# 3_waffling80-NMB_mcu.net
KiCad netlist of a schematic drawn in Altium Designer
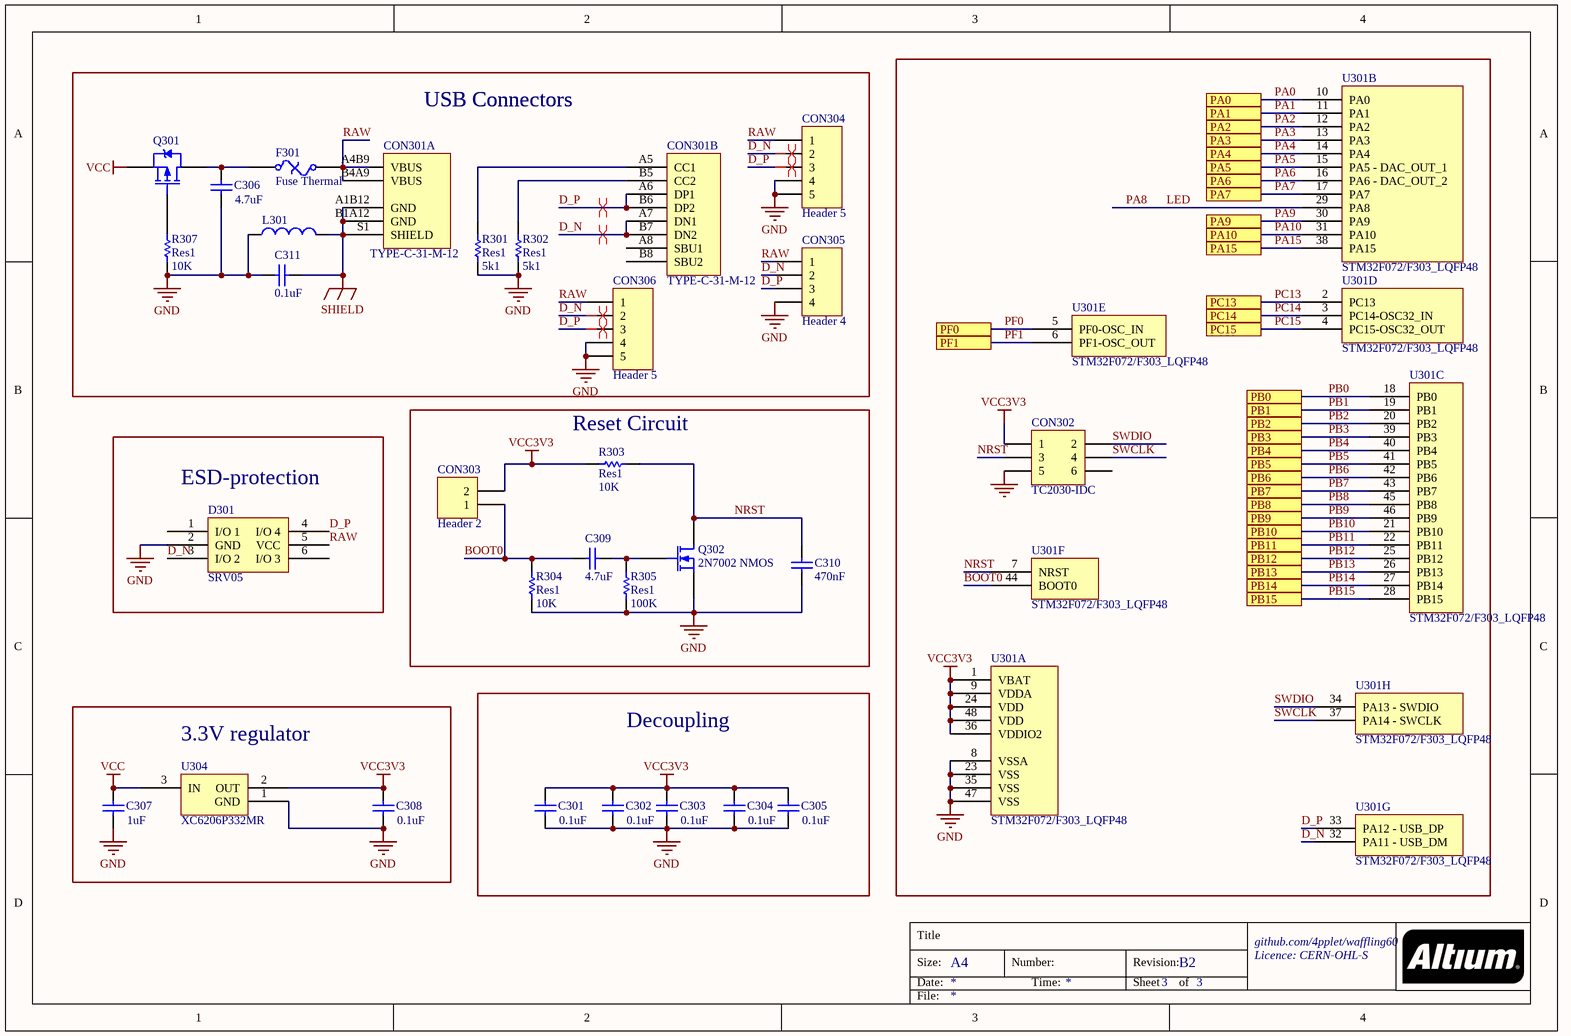
[diagram p0: 3_waffling80-NMB_mcu.SchDoc]

(export (version "E")
  (design (tool "Eeschema 10.0.6"))
  (components
    (comp (ref "C301")
      (value "0.1uF")
      (footprint "C0603[1608]")
      (description "Capacitor")
      (fields (field (name "LCSC PART #") "C14663") (field (name "MRF.PART") "CC0603KRX7R9BB104"))
      (libsource (lib "Miscellaneous Devices") (part "Cap"))
    )
    (comp (ref "C302")
      (value "0.1uF")
      (footprint "C0603[1608]")
      (description "Capacitor")
      (fields (field (name "LCSC PART #") "C14663") (field (name "MRF.PART") "CC0603KRX7R9BB104"))
      (libsource (lib "Miscellaneous Devices") (part "Cap"))
    )
    (comp (ref "C303")
      (value "0.1uF")
      (footprint "C0603[1608]")
      (description "Capacitor")
      (fields (field (name "LCSC PART #") "C14663") (field (name "MRF.PART") "CC0603KRX7R9BB104"))
      (libsource (lib "Miscellaneous Devices") (part "Cap"))
    )
    (comp (ref "C304")
      (value "0.1uF")
      (footprint "C0603[1608]")
      (description "Capacitor")
      (fields (field (name "LCSC PART #") "C14663") (field (name "MRF.PART") "CC0603KRX7R9BB104"))
      (libsource (lib "Miscellaneous Devices") (part "Cap"))
    )
    (comp (ref "C305")
      (value "0.1uF")
      (footprint "C0603[1608]")
      (description "Capacitor")
      (fields (field (name "LCSC PART #") "C14663") (field (name "MRF.PART") "CC0603KRX7R9BB104"))
      (libsource (lib "Miscellaneous Devices") (part "Cap"))
    )
    (comp (ref "C306")
      (value "4.7uF")
      (footprint "C0603[1608]")
      (description "Capacitor")
      (fields (field (name "LCSC PART #") "C19666") (field (name "MRF.PART") "CL10A475KO8NNNC"))
      (libsource (lib "Miscellaneous Devices") (part "Cap"))
    )
    (comp (ref "C307")
      (value "1uF")
      (footprint "C0603[1608]")
      (description "Capacitor")
      (fields (field (name "LCSC PART #") "C15849") (field (name "MRF.PART") "CL10A105KB8NNNC"))
      (libsource (lib "Miscellaneous Devices") (part "Cap"))
    )
    (comp (ref "C308")
      (value "0.1uF")
      (footprint "C0603[1608]")
      (description "Capacitor")
      (fields (field (name "LCSC PART #") "C14663") (field (name "MRF.PART") "CC0603KRX7R9BB104"))
      (libsource (lib "Miscellaneous Devices") (part "Cap"))
    )
    (comp (ref "C309")
      (value "4.7uF")
      (footprint "C0603[1608]")
      (description "Capacitor")
      (fields (field (name "LCSC PART #") "C19666") (field (name "MRF.PART") "CL10A475KO8NNNC"))
      (libsource (lib "Miscellaneous Devices") (part "Cap"))
    )
    (comp (ref "C310")
      (value "470nF")
      (footprint "C0603[1608]")
      (description "Capacitor")
      (fields (field (name "LCSC PART #") "C1623") (field (name "MRF.PART") "CL10B474KA8NNNC"))
      (libsource (lib "Miscellaneous Devices") (part "Cap"))
    )
    (comp (ref "C311")
      (value "0.1uF")
      (footprint "C0603[1608]")
      (description "Capacitor")
      (fields (field (name "LCSC PART #") "C14663") (field (name "MRF.PART") "CC0603KRX7R9BB104"))
      (libsource (lib "Miscellaneous Devices") (part "Cap"))
    )
    (comp (ref "CON301")
      (value "TYPE-C-31-M-12")
      (footprint "TYPE-C-31-M-12")
      (fields (field (name "LCSC PART #") "C165948"))
      (libsource (lib "Schlib1") (part "TYPE-C-31-M-12"))
    )
    (comp (ref "CON302")
      (value "TC2030-IDC")
      (footprint "TC2030-IDC-NL")
      (description "Header, 3-Pin, Dual row")
      (libsource (lib "Miscellaneous Connectors") (part "Header 3X2"))
    )
    (comp (ref "CON303")
      (value "Header 2")
      (footprint "HDR1X2")
      (description "Header, 2-Pin")
      (libsource (lib "Miscellaneous Connectors") (part "Header 2"))
    )
    (comp (ref "CON304")
      (value "Header 5")
      (footprint "UDB_combo_JST_MOLEX")
      (description "JST for USB daughter board")
      (fields (field (name "LCSC PART #") "C160404") (field (name "MRF.PART") "SM04B-SRSS-TB(LF)(SN)"))
      (libsource (lib "Miscellaneous Connectors") (part "Header 5"))
    )
    (comp (ref "CON305")
      (value "Header 4")
      (footprint "HDR1X4")
      (description "Header, 4-Pin")
      (libsource (lib "Miscellaneous Connectors") (part "Header 4"))
    )
    (comp (ref "CON306")
      (value "Header 5")
      (footprint "Molex 781710004")
      (description "JST for USB daughter board")
      (fields (field (name "LCSC PART #") "C588524") (field (name "MRF.PART") "781710004"))
      (libsource (lib "Miscellaneous Connectors") (part "Header 5"))
    )
    (comp (ref "D301")
      (value "SRV05")
      (footprint "SOT-23-6")
      (fields (field (name "LCSC PART #") "C85364") (field (name "MRF.PART") "SRV05-4-P-T7"))
      (libsource (lib "Keebs") (part "SRV05"))
    )
    (comp (ref "F301")
      (value "Fuse Thermal")
      (footprint "C1206[3216]")
      (description "Thermal Fuse")
      (fields (field (name "LCSC PART #") "C135338") (field (name "MRF.PART") "ASMD1206-050"))
      (libsource (lib "Miscellaneous Devices") (part "Fuse Thermal"))
    )
    (comp (ref "L301")
      (value "Inductor")
      (footprint "L0805")
      (fields (field (name "LCSC PART #") "C1015") (field (name "MRF.PART") "GZ2012D101TF"))
      (libsource (lib "Simulation Generic Components") (part "Inductor"))
    )
    (comp (ref "Q301")
      (value "PMOS-2")
      (footprint "SOT-23-3")
      (description "P-Channel Power MOSFET")
      (fields (field (name "LCSC PART #") "C10487") (field (name "MRF.PART") "SI2301CDS-T1-GE3"))
      (libsource (lib "Miscellaneous Devices") (part "PMOS-2"))
    )
    (comp (ref "Q302")
      (value "2N7002 NMOS")
      (footprint "SOT-23-3")
      (description "N-Channel MOSFET")
      (fields (field (name "LCSC PART #") "C8545") (field (name "MRF.PART") "2N7002"))
      (libsource (lib "Miscellaneous Devices") (part "MOSFET-N"))
    )
    (comp (ref "R301")
      (value "Res1")
      (footprint "R0603[1608]")
      (description "Resistor")
      (fields
        (field (name "ALTIUM_VALUE") "5k1")
        (field (name "LCSC PART #") "C23186")
        (field (name "MRF.PART") "0603WAF5101T5E")
      )
      (libsource (lib "Miscellaneous Devices") (part "Res1"))
    )
    (comp (ref "R302")
      (value "Res1")
      (footprint "R0603[1608]")
      (description "Resistor")
      (fields
        (field (name "ALTIUM_VALUE") "5k1")
        (field (name "LCSC PART #") "C23186")
        (field (name "MRF.PART") "0603WAF5101T5E")
      )
      (libsource (lib "Miscellaneous Devices") (part "Res1"))
    )
    (comp (ref "R303")
      (value "Res1")
      (footprint "R0603[1608]")
      (description "Resistor")
      (fields
        (field (name "ALTIUM_VALUE") "10K")
        (field (name "LCSC PART #") "C25804")
        (field (name "MRF.PART") "0603WAF1002T5E")
      )
      (libsource (lib "Miscellaneous Devices") (part "Res1"))
    )
    (comp (ref "R304")
      (value "Res1")
      (footprint "R0603[1608]")
      (description "Resistor")
      (fields
        (field (name "ALTIUM_VALUE") "10K")
        (field (name "LCSC PART #") "C25804")
        (field (name "MRF.PART") "0603WAF1002T5E")
      )
      (libsource (lib "Miscellaneous Devices") (part "Res1"))
    )
    (comp (ref "R305")
      (value "Res1")
      (footprint "R0603[1608]")
      (description "Resistor")
      (fields
        (field (name "ALTIUM_VALUE") "100K")
        (field (name "LCSC PART #") "C25803")
        (field (name "MRF.PART") "0603WAF1003T5E")
      )
      (libsource (lib "Miscellaneous Devices") (part "Res1"))
    )
    (comp (ref "R307")
      (value "Res1")
      (footprint "R0603[1608]")
      (description "Resistor")
      (fields
        (field (name "ALTIUM_VALUE") "10K")
        (field (name "LCSC PART #") "C25804")
        (field (name "MRF.PART") "0603WAF1002T5E")
      )
      (libsource (lib "Miscellaneous Devices") (part "Res1"))
    )
    (comp (ref "U301")
      (value "STM32F072/F303_LQFP48")
      (footprint "STM32 - COMBO 7X7MM")
      (fields (field (name "LCSC PART #") "C915660") (field (name "MRF.PART") "APM32F072CBT6"))
      (libsource (lib "Keebs") (part "STM32F072/F303_LQFP48"))
    )
    (comp (ref "U304")
      (value "XC6206P332MR")
      (footprint "SOT-23-3")
      (fields (field (name "LCSC PART #") "C5446"))
      (libsource (lib "Keebs") (part "SOT23 LDO"))
    )
  )
  (nets
    (net (code "1") (name "/BOOT0") (class "Default")
      (node (ref "C309") (pin "1") (pinfunction "1_1") (pintype "passive"))
      (node (ref "CON303") (pin "1") (pinfunction "1_1") (pintype "passive"))
      (node (ref "R304") (pin "1") (pinfunction "1_1") (pintype "passive"))
      (node (ref "U301") (pin "44") (pinfunction "BOOT0_44") (pintype "passive"))
    )
    (net (code "2") (name "/D_N") (class "Default")
      (node (ref "CON301") (pin "A7") (pinfunction "DN1_A7") (pintype "passive"))
      (node (ref "CON301") (pin "B7") (pinfunction "DN2_B7") (pintype "passive"))
      (node (ref "CON304") (pin "2") (pinfunction "2_2") (pintype "passive"))
      (node (ref "CON305") (pin "2") (pinfunction "2_2") (pintype "passive"))
      (node (ref "CON306") (pin "2") (pinfunction "2_2") (pintype "passive"))
      (node (ref "D301") (pin "3") (pinfunction "I/O_2_3") (pintype "passive"))
      (node (ref "U301") (pin "32") (pinfunction "PA11_-_USB_DM_32") (pintype "passive"))
    )
    (net (code "3") (name "/D_P") (class "Default")
      (node (ref "CON301") (pin "A6") (pinfunction "DP1_A6") (pintype "passive"))
      (node (ref "CON301") (pin "B6") (pinfunction "DP2_B6") (pintype "passive"))
      (node (ref "CON304") (pin "3") (pinfunction "3_3") (pintype "passive"))
      (node (ref "CON305") (pin "3") (pinfunction "3_3") (pintype "passive"))
      (node (ref "CON306") (pin "3") (pinfunction "3_3") (pintype "passive"))
      (node (ref "D301") (pin "4") (pinfunction "I/O_4_4") (pintype "passive"))
      (node (ref "U301") (pin "33") (pinfunction "PA12_-_USB_DP_33") (pintype "passive"))
    )
    (net (code "4") (name "/LED") (class "Default")
      (node (ref "U301") (pin "29") (pinfunction "PA8_29") (pintype "passive"))
    )
    (net (code "5") (name "/NRST") (class "Default")
      (node (ref "C310") (pin "1") (pinfunction "1_1") (pintype "passive"))
      (node (ref "CON302") (pin "3") (pinfunction "3_3") (pintype "passive"))
      (node (ref "Q302") (pin "3") (pinfunction "D_3") (pintype "passive"))
      (node (ref "R303") (pin "2") (pinfunction "2_2") (pintype "passive"))
      (node (ref "U301") (pin "7") (pinfunction "NRST_7") (pintype "passive"))
    )
    (net (code "6") (name "/PA0") (class "Default")
      (node (ref "U301") (pin "10") (pinfunction "PA0_10") (pintype "passive"))
    )
    (net (code "7") (name "/PA1") (class "Default")
      (node (ref "U301") (pin "11") (pinfunction "PA1_11") (pintype "passive"))
    )
    (net (code "8") (name "/PA2") (class "Default")
      (node (ref "U301") (pin "12") (pinfunction "PA2_12") (pintype "passive"))
    )
    (net (code "9") (name "/PA3") (class "Default")
      (node (ref "U301") (pin "13") (pinfunction "PA3_13") (pintype "passive"))
    )
    (net (code "10") (name "/PA4") (class "Default")
      (node (ref "U301") (pin "14") (pinfunction "PA4_14") (pintype "passive"))
    )
    (net (code "11") (name "/PA5") (class "Default")
      (node (ref "U301") (pin "15") (pinfunction "PA5_-_DAC_OUT_1_15") (pintype "passive"))
    )
    (net (code "12") (name "/PA6") (class "Default")
      (node (ref "U301") (pin "16") (pinfunction "PA6_-_DAC_OUT_2_16") (pintype "passive"))
    )
    (net (code "13") (name "/PA7") (class "Default")
      (node (ref "U301") (pin "17") (pinfunction "PA7_17") (pintype "passive"))
    )
    (net (code "14") (name "/PA9") (class "Default")
      (node (ref "U301") (pin "30") (pinfunction "PA9_30") (pintype "passive"))
    )
    (net (code "15") (name "/PA10") (class "Default")
      (node (ref "U301") (pin "31") (pinfunction "PA10_31") (pintype "passive"))
    )
    (net (code "16") (name "/PA15") (class "Default")
      (node (ref "U301") (pin "38") (pinfunction "PA15_38") (pintype "passive"))
    )
    (net (code "17") (name "/PB0") (class "Default")
      (node (ref "U301") (pin "18") (pinfunction "PB0_18") (pintype "passive"))
    )
    (net (code "18") (name "/PB1") (class "Default")
      (node (ref "U301") (pin "19") (pinfunction "PB1_19") (pintype "passive"))
    )
    (net (code "19") (name "/PB2") (class "Default")
      (node (ref "U301") (pin "20") (pinfunction "PB2_20") (pintype "passive"))
    )
    (net (code "20") (name "/PB3") (class "Default")
      (node (ref "U301") (pin "39") (pinfunction "PB3_39") (pintype "passive"))
    )
    (net (code "21") (name "/PB4") (class "Default")
      (node (ref "U301") (pin "40") (pinfunction "PB4_40") (pintype "passive"))
    )
    (net (code "22") (name "/PB5") (class "Default")
      (node (ref "U301") (pin "41") (pinfunction "PB5_41") (pintype "passive"))
    )
    (net (code "23") (name "/PB6") (class "Default")
      (node (ref "U301") (pin "42") (pinfunction "PB6_42") (pintype "passive"))
    )
    (net (code "24") (name "/PB7") (class "Default")
      (node (ref "U301") (pin "43") (pinfunction "PB7_43") (pintype "passive"))
    )
    (net (code "25") (name "/PB8") (class "Default")
      (node (ref "U301") (pin "45") (pinfunction "PB8_45") (pintype "passive"))
    )
    (net (code "26") (name "/PB9") (class "Default")
      (node (ref "U301") (pin "46") (pinfunction "PB9_46") (pintype "passive"))
    )
    (net (code "27") (name "/PB10") (class "Default")
      (node (ref "U301") (pin "21") (pinfunction "PB10_21") (pintype "passive"))
    )
    (net (code "28") (name "/PB11") (class "Default")
      (node (ref "U301") (pin "22") (pinfunction "PB11_22") (pintype "passive"))
    )
    (net (code "29") (name "/PB12") (class "Default")
      (node (ref "U301") (pin "25") (pinfunction "PB12_25") (pintype "passive"))
    )
    (net (code "30") (name "/PB13") (class "Default")
      (node (ref "U301") (pin "26") (pinfunction "PB13_26") (pintype "passive"))
    )
    (net (code "31") (name "/PB14") (class "Default")
      (node (ref "U301") (pin "27") (pinfunction "PB14_27") (pintype "passive"))
    )
    (net (code "32") (name "/PB15") (class "Default")
      (node (ref "U301") (pin "28") (pinfunction "PB15_28") (pintype "passive"))
    )
    (net (code "33") (name "/PC13") (class "Default")
      (node (ref "U301") (pin "2") (pinfunction "PC13_2") (pintype "passive"))
    )
    (net (code "34") (name "/PC14") (class "Default")
      (node (ref "U301") (pin "3") (pinfunction "PC14-OSC32_IN_3") (pintype "passive"))
    )
    (net (code "35") (name "/PC15") (class "Default")
      (node (ref "U301") (pin "4") (pinfunction "PC15-OSC32_OUT_4") (pintype "passive"))
    )
    (net (code "36") (name "/PF0") (class "Default")
      (node (ref "U301") (pin "5") (pinfunction "PF0-OSC_IN_5") (pintype "passive"))
    )
    (net (code "37") (name "/PF1") (class "Default")
      (node (ref "U301") (pin "6") (pinfunction "PF1-OSC_OUT_6") (pintype "passive"))
    )
    (net (code "38") (name "/RAW") (class "Default")
      (node (ref "CON301") (pin "A4B9") (pinfunction "VBUS_A4B9") (pintype "passive"))
      (node (ref "CON301") (pin "B4A9") (pinfunction "VBUS_B4A9") (pintype "passive"))
      (node (ref "CON304") (pin "1") (pinfunction "1_1") (pintype "passive"))
      (node (ref "CON305") (pin "1") (pinfunction "1_1") (pintype "passive"))
      (node (ref "CON306") (pin "1") (pinfunction "1_1") (pintype "passive"))
      (node (ref "D301") (pin "5") (pinfunction "VCC_5") (pintype "passive"))
      (node (ref "F301") (pin "2") (pinfunction "2_2") (pintype "passive"))
    )
    (net (code "39") (name "/SWCLK") (class "Default")
      (node (ref "CON302") (pin "4") (pinfunction "4_4") (pintype "passive"))
      (node (ref "U301") (pin "37") (pinfunction "PA14_-_SWCLK_37") (pintype "passive"))
    )
    (net (code "40") (name "/SWDIO") (class "Default")
      (node (ref "CON302") (pin "2") (pinfunction "2_2") (pintype "passive"))
      (node (ref "U301") (pin "34") (pinfunction "PA13_-_SWDIO_34") (pintype "passive"))
    )
    (net (code "41") (name "GND") (class "Default")
      (node (ref "C301") (pin "1") (pinfunction "1_1") (pintype "passive"))
      (node (ref "C302") (pin "1") (pinfunction "1_1") (pintype "passive"))
      (node (ref "C303") (pin "1") (pinfunction "1_1") (pintype "passive"))
      (node (ref "C304") (pin "1") (pinfunction "1_1") (pintype "passive"))
      (node (ref "C305") (pin "1") (pinfunction "1_1") (pintype "passive"))
      (node (ref "C306") (pin "1") (pinfunction "1_1") (pintype "passive"))
      (node (ref "C307") (pin "1") (pinfunction "1_1") (pintype "passive"))
      (node (ref "C308") (pin "1") (pinfunction "1_1") (pintype "passive"))
      (node (ref "C310") (pin "2") (pinfunction "2_2") (pintype "passive"))
      (node (ref "C311") (pin "1") (pinfunction "1_1") (pintype "passive"))
      (node (ref "CON302") (pin "5") (pinfunction "5_5") (pintype "passive"))
      (node (ref "CON304") (pin "4") (pinfunction "4_4") (pintype "passive"))
      (node (ref "CON304") (pin "5") (pinfunction "5_5") (pintype "passive"))
      (node (ref "CON305") (pin "4") (pinfunction "4_4") (pintype "passive"))
      (node (ref "CON306") (pin "4") (pinfunction "4_4") (pintype "passive"))
      (node (ref "CON306") (pin "5") (pinfunction "5_5") (pintype "passive"))
      (node (ref "D301") (pin "2") (pinfunction "GND_2") (pintype "passive"))
      (node (ref "L301") (pin "1") (pinfunction "1_1") (pintype "passive"))
      (node (ref "Q302") (pin "2") (pinfunction "S_2") (pintype "passive"))
      (node (ref "R301") (pin "2") (pinfunction "2_2") (pintype "passive"))
      (node (ref "R302") (pin "2") (pinfunction "2_2") (pintype "passive"))
      (node (ref "R304") (pin "2") (pinfunction "2_2") (pintype "passive"))
      (node (ref "R305") (pin "2") (pinfunction "2_2") (pintype "passive"))
      (node (ref "R307") (pin "2") (pinfunction "2_2") (pintype "passive"))
      (node (ref "U301") (pin "23") (pinfunction "VSS_23") (pintype "passive"))
      (node (ref "U301") (pin "35") (pinfunction "VSS_35") (pintype "passive"))
      (node (ref "U301") (pin "47") (pinfunction "VSS_47") (pintype "passive"))
      (node (ref "U301") (pin "8") (pinfunction "VSSA_8") (pintype "passive"))
      (node (ref "U304") (pin "1") (pinfunction "GND_1") (pintype "passive"))
    )
    (net (code "42") (name "Net-(CON301B-CC1)") (class "Default")
      (node (ref "CON301") (pin "A5") (pinfunction "CC1_A5") (pintype "passive"))
      (node (ref "R301") (pin "1") (pinfunction "1_1") (pintype "passive"))
    )
    (net (code "43") (name "Net-(CON301B-CC2)") (class "Default")
      (node (ref "CON301") (pin "B5") (pinfunction "CC2_B5") (pintype "passive"))
      (node (ref "R302") (pin "1") (pinfunction "1_1") (pintype "passive"))
    )
    (net (code "44") (name "Net-(Q301-D)") (class "Default")
      (node (ref "C306") (pin "2") (pinfunction "2_2") (pintype "passive"))
      (node (ref "F301") (pin "1") (pinfunction "1_1") (pintype "passive"))
      (node (ref "Q301") (pin "3") (pinfunction "D_3") (pintype "passive"))
    )
    (net (code "45") (name "Net-(Q301-G)") (class "Default")
      (node (ref "Q301") (pin "1") (pinfunction "G_1") (pintype "passive"))
      (node (ref "R307") (pin "1") (pinfunction "1_1") (pintype "passive"))
    )
    (net (code "46") (name "Net-(Q302-G)") (class "Default")
      (node (ref "C309") (pin "2") (pinfunction "2_2") (pintype "passive"))
      (node (ref "Q302") (pin "1") (pinfunction "G_1") (pintype "passive"))
      (node (ref "R305") (pin "1") (pinfunction "1_1") (pintype "passive"))
    )
    (net (code "47") (name "SHIELD") (class "Default")
      (node (ref "C311") (pin "2") (pinfunction "2_2") (pintype "passive"))
      (node (ref "CON301") (pin "A1B12") (pinfunction "GND_A1B12") (pintype "passive"))
      (node (ref "CON301") (pin "B1A12") (pinfunction "GND_B1A12") (pintype "passive"))
      (node (ref "CON301") (pin "S1") (pinfunction "SHIELD_S1") (pintype "passive"))
      (node (ref "L301") (pin "2") (pinfunction "2_2") (pintype "passive"))
    )
    (net (code "48") (name "VCC") (class "Default")
      (node (ref "C307") (pin "2") (pinfunction "2_2") (pintype "passive"))
      (node (ref "Q301") (pin "2") (pinfunction "S_2") (pintype "passive"))
      (node (ref "U304") (pin "3") (pinfunction "IN_3") (pintype "passive"))
    )
    (net (code "49") (name "VCC3V3") (class "Default")
      (node (ref "C301") (pin "2") (pinfunction "2_2") (pintype "passive"))
      (node (ref "C302") (pin "2") (pinfunction "2_2") (pintype "passive"))
      (node (ref "C303") (pin "2") (pinfunction "2_2") (pintype "passive"))
      (node (ref "C304") (pin "2") (pinfunction "2_2") (pintype "passive"))
      (node (ref "C305") (pin "2") (pinfunction "2_2") (pintype "passive"))
      (node (ref "C308") (pin "2") (pinfunction "2_2") (pintype "passive"))
      (node (ref "CON302") (pin "1") (pinfunction "1_1") (pintype "passive"))
      (node (ref "CON303") (pin "2") (pinfunction "2_2") (pintype "passive"))
      (node (ref "R303") (pin "1") (pinfunction "1_1") (pintype "passive"))
      (node (ref "U301") (pin "1") (pinfunction "VBAT_1") (pintype "passive"))
      (node (ref "U301") (pin "24") (pinfunction "VDD_24") (pintype "passive"))
      (node (ref "U301") (pin "36") (pinfunction "VDDIO2_36") (pintype "passive"))
      (node (ref "U301") (pin "48") (pinfunction "VDD_48") (pintype "passive"))
      (node (ref "U301") (pin "9") (pinfunction "VDDA_9") (pintype "passive"))
      (node (ref "U304") (pin "2") (pinfunction "OUT_2") (pintype "passive"))
    )
    (net (code "50") (name "unconnected-(CON301B-SBU1-PadA8)") (class "Default")
      (node (ref "CON301") (pin "A8") (pinfunction "SBU1_A8") (pintype "passive"))
    )
    (net (code "51") (name "unconnected-(CON301B-SBU2-PadB8)") (class "Default")
      (node (ref "CON301") (pin "B8") (pinfunction "SBU2_B8") (pintype "passive"))
    )
    (net (code "52") (name "unconnected-(CON302-Pad6)") (class "Default")
      (node (ref "CON302") (pin "6") (pinfunction "6_6") (pintype "passive"))
    )
    (net (code "53") (name "unconnected-(D301-I{slash}O_1-Pad1)") (class "Default")
      (node (ref "D301") (pin "1") (pinfunction "I/O_1_1") (pintype "passive"))
    )
    (net (code "54") (name "unconnected-(D301-I{slash}O_3-Pad6)") (class "Default")
      (node (ref "D301") (pin "6") (pinfunction "I/O_3_6") (pintype "passive"))
    )
  )
)
